# eeZeePower.net
KiCad netlist of a schematic drawn in EAGLE
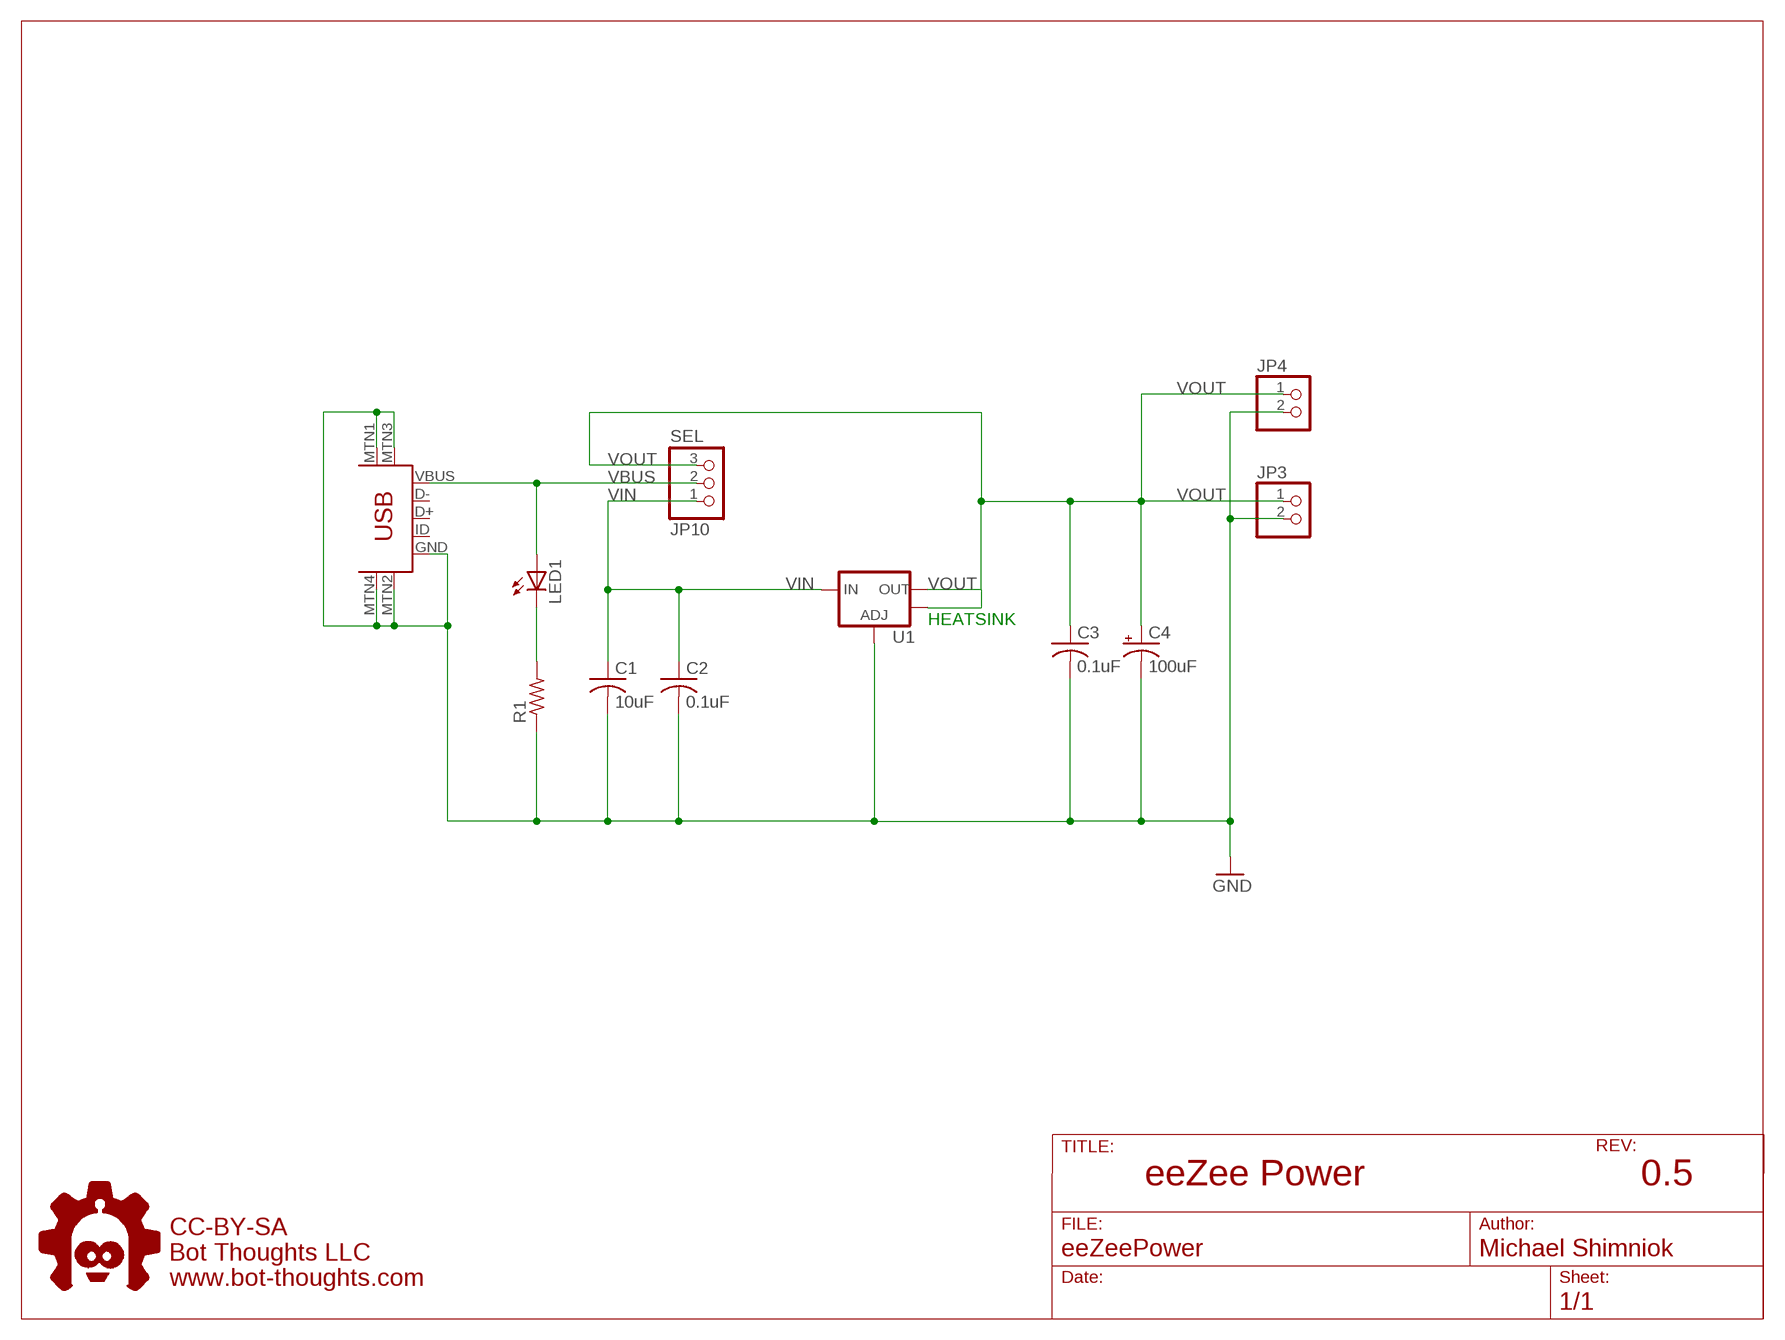
[diagram p0: schematic, sheet 1]

(export (version "E")
  (design (tool "Eeschema 10.0.6"))
  (components
    (comp (ref "C1")
      (value "10uF")
      (footprint "eagle-import:C1206")
      (libsource (lib "eagle-import") (part "C-USC1206"))
    )
    (comp (ref "C2")
      (value "0.1uF")
      (footprint "eagle-import:C0603")
      (libsource (lib "eagle-import") (part "C-USC0603"))
    )
    (comp (ref "C3")
      (value "0.1uF")
      (footprint "eagle-import:C0603")
      (libsource (lib "eagle-import") (part "C-USC0603"))
    )
    (comp (ref "C4")
      (value "100uF")
      (footprint "eagle-import:SMC_B")
      (libsource (lib "eagle-import") (part "CPOL-USSMCB"))
    )
    (comp (ref "JP3")
      (value "PINHD-1X02_2.54-S")
      (footprint "eagle-import:1X02-S")
      (libsource (lib "eagle-import") (part "PINHD-1X02_2.54-S"))
    )
    (comp (ref "JP4")
      (value "PINHD-1X02_2.54-S")
      (footprint "eagle-import:1X02-S")
      (libsource (lib "eagle-import") (part "PINHD-1X02_2.54-S"))
    )
    (comp (ref "JP10")
      (value "SEL")
      (footprint "eagle-import:1X03-S")
      (libsource (lib "eagle-import") (part "PINHD-1X03_2.54-S"))
    )
    (comp (ref "LED1")
      (value "LEDCHIPLED_1206")
      (footprint "eagle-import:CHIPLED_1206")
      (libsource (lib "eagle-import") (part "LEDCHIPLED_1206"))
    )
    (comp (ref "R1")
      (value "R-US_R0603")
      (footprint "eagle-import:R0603")
      (libsource (lib "eagle-import") (part "R-US_R0603"))
    )
    (comp (ref "U$1")
      (value "USB-MINIB-5PIN")
      (footprint "eagle-import:USB-MINIB")
      (libsource (lib "eagle-import") (part "USB-MINIB-5PIN"))
    )
    (comp (ref "U$3")
      (value "BOT-THOUGHTS-LOGO-MD")
      (footprint "eagle-import:BTLOGOM")
      (libsource (lib "eagle-import") (part "BOT-THOUGHTS-LOGO-MD"))
    )
    (comp (ref "U1")
      (value "V_REG_LM1117SOT223")
      (footprint "eagle-import:SOT223")
      (libsource (lib "eagle-import") (part "V_REG_LM1117SOT223"))
    )
  )
  (nets
    (net (code "1") (name "/VBUS") (class "Default")
      (node (ref "JP10") (pin "2") (pinfunction "2_2") (pintype "passive"))
      (node (ref "LED1") (pin "A") (pinfunction "A_A") (pintype "passive"))
      (node (ref "U$1") (pin "VBUS") (pinfunction "VBUS_VBUS") (pintype "bidirectional"))
    )
    (net (code "2") (name "/VIN") (class "Default")
      (node (ref "C1") (pin "1") (pinfunction "1_1") (pintype "passive"))
      (node (ref "C2") (pin "1") (pinfunction "1_1") (pintype "passive"))
      (node (ref "JP10") (pin "1") (pinfunction "1_1") (pintype "passive"))
      (node (ref "U1") (pin "3") (pinfunction "IN_3") (pintype "input"))
    )
    (net (code "3") (name "/VOUT") (class "Default")
      (node (ref "C3") (pin "1") (pinfunction "1_1") (pintype "passive"))
      (node (ref "C4") (pin "+") (pinfunction "+_+") (pintype "passive"))
      (node (ref "JP10") (pin "3") (pinfunction "3_3") (pintype "passive"))
      (node (ref "JP3") (pin "1") (pinfunction "1_1") (pintype "passive"))
      (node (ref "JP4") (pin "1") (pinfunction "1_1") (pintype "passive"))
      (node (ref "U1") (pin "2") (pinfunction "OUT_2") (pintype "output"))
      (node (ref "U1") (pin "4") (pinfunction "OUT_4") (pintype "output"))
    )
    (net (code "4") (name "GND") (class "Default")
      (node (ref "C1") (pin "2") (pinfunction "2_2") (pintype "passive"))
      (node (ref "C2") (pin "2") (pinfunction "2_2") (pintype "passive"))
      (node (ref "C3") (pin "2") (pinfunction "2_2") (pintype "passive"))
      (node (ref "C4") (pin "-") (pinfunction "-_-") (pintype "passive"))
      (node (ref "JP3") (pin "2") (pinfunction "2_2") (pintype "passive"))
      (node (ref "JP4") (pin "2") (pinfunction "2_2") (pintype "passive"))
      (node (ref "R1") (pin "1") (pinfunction "1_1") (pintype "passive"))
      (node (ref "U$1") (pin "GND") (pinfunction "GND_GND") (pintype "bidirectional"))
      (node (ref "U$1") (pin "MTN1") (pinfunction "MTN2_MTN1") (pintype "bidirectional"))
      (node (ref "U$1") (pin "MTN2") (pinfunction "MTN3_MTN2") (pintype "bidirectional"))
      (node (ref "U$1") (pin "MTN3") (pinfunction "MTN1_MTN3") (pintype "bidirectional"))
      (node (ref "U$1") (pin "MTN4") (pinfunction "MTN4_MTN4") (pintype "bidirectional"))
      (node (ref "U1") (pin "1") (pinfunction "ADJ_1") (pintype "input"))
    )
    (net (code "5") (name "Net-(LED1-PadC)") (class "Default")
      (node (ref "LED1") (pin "C") (pinfunction "C_C") (pintype "passive"))
      (node (ref "R1") (pin "2") (pinfunction "2_2") (pintype "passive"))
    )
    (net (code "6") (name "unconnected-(U$1-PadD+)") (class "Default")
      (node (ref "U$1") (pin "D+") (pinfunction "D+_D+") (pintype "bidirectional"))
    )
    (net (code "7") (name "unconnected-(U$1-PadD-)") (class "Default")
      (node (ref "U$1") (pin "D-") (pinfunction "D-_D-") (pintype "bidirectional"))
    )
    (net (code "8") (name "unconnected-(U$1-PadID)") (class "Default")
      (node (ref "U$1") (pin "ID") (pinfunction "ID_ID") (pintype "bidirectional"))
    )
  )
)
